# Buton.net
KiCad netlist of a schematic drawn in Altium Designer
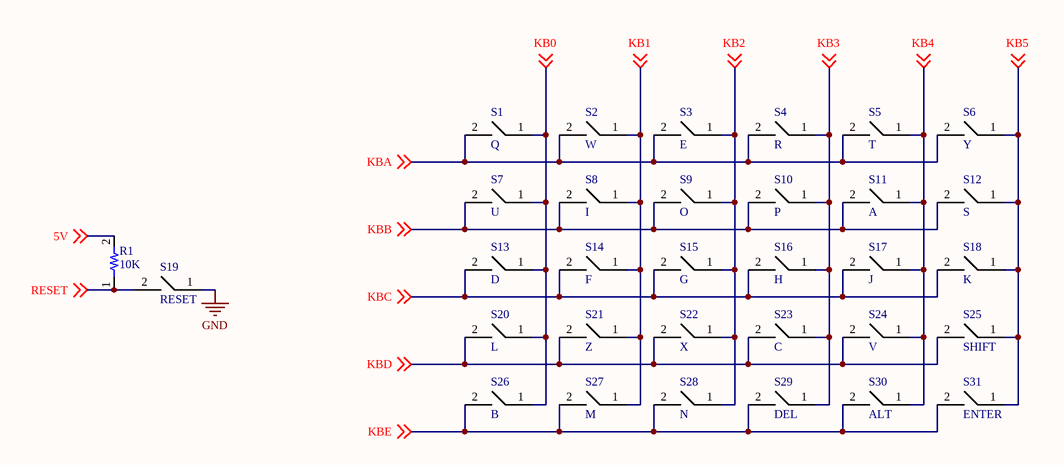
[diagram p0: Buton.SchDoc]

(export (version "E")
  (design (tool "Eeschema 10.0.6"))
  (components
    (comp (ref "R1")
      (value "10K")
      (footprint "0603 Resistor")
      (description "Resistor")
      (fields
        (field (name "MANUFACTURER_PART_NUMBER") "CPF0603B100RE1")
        (field (name "MOUSER PART NUMBER") "279-CPF0603B100RE1")
      )
      (libsource (lib "uAltiumLib") (part "0603 Resistor"))
    )
    (comp (ref "S1")
      (value "Q")
      (footprint "TACT SWITCH SMD")
      (fields (field (name "MP") "B3F-1000") (field (name "MF") "Omron"))
      (libsource (lib "uAltiumLib") (part "TACT SWITCH SMD"))
    )
    (comp (ref "S2")
      (value "W")
      (footprint "TACT SWITCH SMD")
      (fields (field (name "MP") "B3F-1000") (field (name "MF") "Omron"))
      (libsource (lib "uAltiumLib") (part "TACT SWITCH SMD"))
    )
    (comp (ref "S3")
      (value "E")
      (footprint "TACT SWITCH SMD")
      (fields (field (name "MP") "B3F-1000") (field (name "MF") "Omron"))
      (libsource (lib "uAltiumLib") (part "TACT SWITCH SMD"))
    )
    (comp (ref "S4")
      (value "R")
      (footprint "TACT SWITCH SMD")
      (fields (field (name "MP") "B3F-1000") (field (name "MF") "Omron"))
      (libsource (lib "uAltiumLib") (part "TACT SWITCH SMD"))
    )
    (comp (ref "S5")
      (value "T")
      (footprint "TACT SWITCH SMD")
      (fields (field (name "MP") "B3F-1000") (field (name "MF") "Omron"))
      (libsource (lib "uAltiumLib") (part "TACT SWITCH SMD"))
    )
    (comp (ref "S6")
      (value "Y")
      (footprint "TACT SWITCH SMD")
      (fields (field (name "MP") "B3F-1000") (field (name "MF") "Omron"))
      (libsource (lib "uAltiumLib") (part "TACT SWITCH SMD"))
    )
    (comp (ref "S7")
      (value "U")
      (footprint "TACT SWITCH SMD")
      (fields (field (name "MP") "B3F-1000") (field (name "MF") "Omron"))
      (libsource (lib "uAltiumLib") (part "TACT SWITCH SMD"))
    )
    (comp (ref "S8")
      (value "I")
      (footprint "TACT SWITCH SMD")
      (fields (field (name "MP") "B3F-1000") (field (name "MF") "Omron"))
      (libsource (lib "uAltiumLib") (part "TACT SWITCH SMD"))
    )
    (comp (ref "S9")
      (value "O")
      (footprint "TACT SWITCH SMD")
      (fields (field (name "MP") "B3F-1000") (field (name "MF") "Omron"))
      (libsource (lib "uAltiumLib") (part "TACT SWITCH SMD"))
    )
    (comp (ref "S10")
      (value "P")
      (footprint "TACT SWITCH SMD")
      (fields (field (name "MP") "B3F-1000") (field (name "MF") "Omron"))
      (libsource (lib "uAltiumLib") (part "TACT SWITCH SMD"))
    )
    (comp (ref "S11")
      (value "A")
      (footprint "TACT SWITCH SMD")
      (fields (field (name "MP") "B3F-1000") (field (name "MF") "Omron"))
      (libsource (lib "uAltiumLib") (part "TACT SWITCH SMD"))
    )
    (comp (ref "S12")
      (value "S")
      (footprint "TACT SWITCH SMD")
      (fields (field (name "MP") "B3F-1000") (field (name "MF") "Omron"))
      (libsource (lib "uAltiumLib") (part "TACT SWITCH SMD"))
    )
    (comp (ref "S13")
      (value "D")
      (footprint "TACT SWITCH SMD")
      (fields (field (name "MP") "B3F-1000") (field (name "MF") "Omron"))
      (libsource (lib "uAltiumLib") (part "TACT SWITCH SMD"))
    )
    (comp (ref "S14")
      (value "F")
      (footprint "TACT SWITCH SMD")
      (fields (field (name "MP") "B3F-1000") (field (name "MF") "Omron"))
      (libsource (lib "uAltiumLib") (part "TACT SWITCH SMD"))
    )
    (comp (ref "S15")
      (value "G")
      (footprint "TACT SWITCH SMD")
      (fields (field (name "MP") "B3F-1000") (field (name "MF") "Omron"))
      (libsource (lib "uAltiumLib") (part "TACT SWITCH SMD"))
    )
    (comp (ref "S16")
      (value "H")
      (footprint "TACT SWITCH SMD")
      (fields (field (name "MP") "B3F-1000") (field (name "MF") "Omron"))
      (libsource (lib "uAltiumLib") (part "TACT SWITCH SMD"))
    )
    (comp (ref "S17")
      (value "J")
      (footprint "TACT SWITCH SMD")
      (fields (field (name "MP") "B3F-1000") (field (name "MF") "Omron"))
      (libsource (lib "uAltiumLib") (part "TACT SWITCH SMD"))
    )
    (comp (ref "S18")
      (value "K")
      (footprint "TACT SWITCH SMD")
      (fields (field (name "MP") "B3F-1000") (field (name "MF") "Omron"))
      (libsource (lib "uAltiumLib") (part "TACT SWITCH SMD"))
    )
    (comp (ref "S19")
      (value "RESET")
      (footprint "TACT SWITCH SMD")
      (fields (field (name "MP") "B3F-1000") (field (name "MF") "Omron"))
      (libsource (lib "uAltiumLib") (part "TACT SWITCH SMD"))
    )
    (comp (ref "S20")
      (value "L")
      (footprint "TACT SWITCH SMD")
      (fields (field (name "MP") "B3F-1000") (field (name "MF") "Omron"))
      (libsource (lib "uAltiumLib") (part "TACT SWITCH SMD"))
    )
    (comp (ref "S21")
      (value "Z")
      (footprint "TACT SWITCH SMD")
      (fields (field (name "MP") "B3F-1000") (field (name "MF") "Omron"))
      (libsource (lib "uAltiumLib") (part "TACT SWITCH SMD"))
    )
    (comp (ref "S22")
      (value "X")
      (footprint "TACT SWITCH SMD")
      (fields (field (name "MP") "B3F-1000") (field (name "MF") "Omron"))
      (libsource (lib "uAltiumLib") (part "TACT SWITCH SMD"))
    )
    (comp (ref "S23")
      (value "C")
      (footprint "TACT SWITCH SMD")
      (fields (field (name "MP") "B3F-1000") (field (name "MF") "Omron"))
      (libsource (lib "uAltiumLib") (part "TACT SWITCH SMD"))
    )
    (comp (ref "S24")
      (value "V")
      (footprint "TACT SWITCH SMD")
      (fields (field (name "MP") "B3F-1000") (field (name "MF") "Omron"))
      (libsource (lib "uAltiumLib") (part "TACT SWITCH SMD"))
    )
    (comp (ref "S25")
      (value "SHIFT")
      (footprint "TACT SWITCH SMD")
      (fields (field (name "MP") "B3F-1000") (field (name "MF") "Omron"))
      (libsource (lib "uAltiumLib") (part "TACT SWITCH SMD"))
    )
    (comp (ref "S26")
      (value "B")
      (footprint "TACT SWITCH SMD")
      (fields (field (name "MP") "B3F-1000") (field (name "MF") "Omron"))
      (libsource (lib "uAltiumLib") (part "TACT SWITCH SMD"))
    )
    (comp (ref "S27")
      (value "M")
      (footprint "TACT SWITCH SMD")
      (fields (field (name "MP") "B3F-1000") (field (name "MF") "Omron"))
      (libsource (lib "uAltiumLib") (part "TACT SWITCH SMD"))
    )
    (comp (ref "S28")
      (value "N")
      (footprint "TACT SWITCH SMD")
      (fields (field (name "MP") "B3F-1000") (field (name "MF") "Omron"))
      (libsource (lib "uAltiumLib") (part "TACT SWITCH SMD"))
    )
    (comp (ref "S29")
      (value "DEL")
      (footprint "TACT SWITCH SMD")
      (fields (field (name "MP") "B3F-1000") (field (name "MF") "Omron"))
      (libsource (lib "uAltiumLib") (part "TACT SWITCH SMD"))
    )
    (comp (ref "S30")
      (value "ALT")
      (footprint "TACT SWITCH SMD")
      (fields (field (name "MP") "B3F-1000") (field (name "MF") "Omron"))
      (libsource (lib "uAltiumLib") (part "TACT SWITCH SMD"))
    )
    (comp (ref "S31")
      (value "ENTER")
      (footprint "TACT SWITCH SMD")
      (fields (field (name "MP") "B3F-1000") (field (name "MF") "Omron"))
      (libsource (lib "uAltiumLib") (part "TACT SWITCH SMD"))
    )
  )
  (nets
    (net (code "1") (name "5V") (class "Default")
      (node (ref "R1") (pin "2") (pinfunction "2_2") (pintype "passive"))
    )
    (net (code "2") (name "GND") (class "Default") (node (ref "S19") (pin "1") (pintype "passive")))
    (net (code "3") (name "KB0") (class "Default")
      (node (ref "S1") (pin "1") (pintype "passive"))
      (node (ref "S13") (pin "1") (pintype "passive"))
      (node (ref "S20") (pin "1") (pintype "passive"))
      (node (ref "S26") (pin "1") (pintype "passive"))
      (node (ref "S7") (pin "1") (pintype "passive"))
    )
    (net (code "4") (name "KB1") (class "Default")
      (node (ref "S14") (pin "1") (pintype "passive"))
      (node (ref "S2") (pin "1") (pintype "passive"))
      (node (ref "S21") (pin "1") (pintype "passive"))
      (node (ref "S27") (pin "1") (pintype "passive"))
      (node (ref "S8") (pin "1") (pintype "passive"))
    )
    (net (code "5") (name "KB2") (class "Default")
      (node (ref "S15") (pin "1") (pintype "passive"))
      (node (ref "S22") (pin "1") (pintype "passive"))
      (node (ref "S28") (pin "1") (pintype "passive"))
      (node (ref "S3") (pin "1") (pintype "passive"))
      (node (ref "S9") (pin "1") (pintype "passive"))
    )
    (net (code "6") (name "KB3") (class "Default")
      (node (ref "S10") (pin "1") (pintype "passive"))
      (node (ref "S16") (pin "1") (pintype "passive"))
      (node (ref "S23") (pin "1") (pintype "passive"))
      (node (ref "S29") (pin "1") (pintype "passive"))
      (node (ref "S4") (pin "1") (pintype "passive"))
    )
    (net (code "7") (name "KB4") (class "Default")
      (node (ref "S11") (pin "1") (pintype "passive"))
      (node (ref "S17") (pin "1") (pintype "passive"))
      (node (ref "S24") (pin "1") (pintype "passive"))
      (node (ref "S30") (pin "1") (pintype "passive"))
      (node (ref "S5") (pin "1") (pintype "passive"))
    )
    (net (code "8") (name "KB5") (class "Default")
      (node (ref "S12") (pin "1") (pintype "passive"))
      (node (ref "S18") (pin "1") (pintype "passive"))
      (node (ref "S25") (pin "1") (pintype "passive"))
      (node (ref "S31") (pin "1") (pintype "passive"))
      (node (ref "S6") (pin "1") (pintype "passive"))
    )
    (net (code "9") (name "KBA") (class "Default")
      (node (ref "S1") (pin "2") (pintype "passive"))
      (node (ref "S2") (pin "2") (pintype "passive"))
      (node (ref "S3") (pin "2") (pintype "passive"))
      (node (ref "S4") (pin "2") (pintype "passive"))
      (node (ref "S5") (pin "2") (pintype "passive"))
      (node (ref "S6") (pin "2") (pintype "passive"))
    )
    (net (code "10") (name "KBB") (class "Default")
      (node (ref "S10") (pin "2") (pintype "passive"))
      (node (ref "S11") (pin "2") (pintype "passive"))
      (node (ref "S12") (pin "2") (pintype "passive"))
      (node (ref "S7") (pin "2") (pintype "passive"))
      (node (ref "S8") (pin "2") (pintype "passive"))
      (node (ref "S9") (pin "2") (pintype "passive"))
    )
    (net (code "11") (name "KBC") (class "Default")
      (node (ref "S13") (pin "2") (pintype "passive"))
      (node (ref "S14") (pin "2") (pintype "passive"))
      (node (ref "S15") (pin "2") (pintype "passive"))
      (node (ref "S16") (pin "2") (pintype "passive"))
      (node (ref "S17") (pin "2") (pintype "passive"))
      (node (ref "S18") (pin "2") (pintype "passive"))
    )
    (net (code "12") (name "KBD") (class "Default")
      (node (ref "S20") (pin "2") (pintype "passive"))
      (node (ref "S21") (pin "2") (pintype "passive"))
      (node (ref "S22") (pin "2") (pintype "passive"))
      (node (ref "S23") (pin "2") (pintype "passive"))
      (node (ref "S24") (pin "2") (pintype "passive"))
      (node (ref "S25") (pin "2") (pintype "passive"))
    )
    (net (code "13") (name "KBE") (class "Default")
      (node (ref "S26") (pin "2") (pintype "passive"))
      (node (ref "S27") (pin "2") (pintype "passive"))
      (node (ref "S28") (pin "2") (pintype "passive"))
      (node (ref "S29") (pin "2") (pintype "passive"))
      (node (ref "S30") (pin "2") (pintype "passive"))
      (node (ref "S31") (pin "2") (pintype "passive"))
    )
    (net (code "14") (name "RESET") (class "Default")
      (node (ref "R1") (pin "1") (pinfunction "1_1") (pintype "passive"))
      (node (ref "S19") (pin "2") (pintype "passive"))
    )
  )
)
